# rc2014_6809.net
KiCad netlist of a schematic drawn in EAGLE
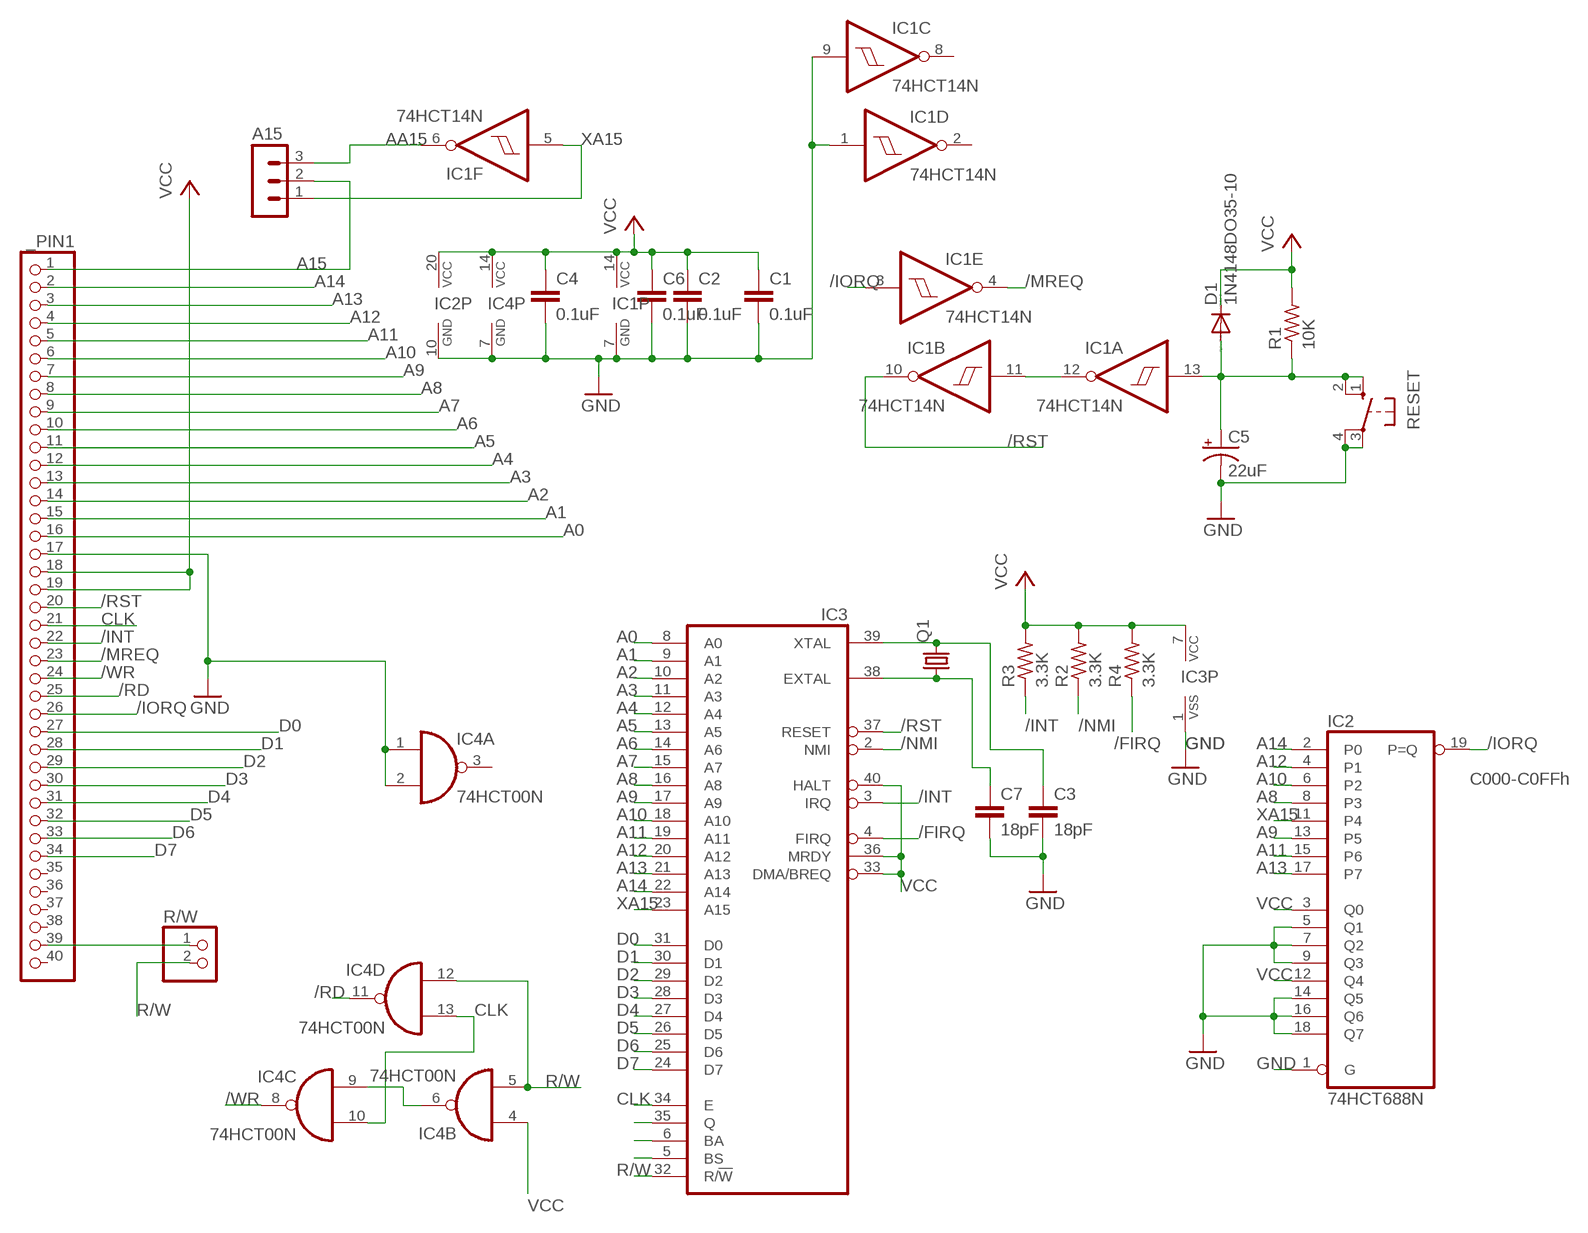
[diagram p0: schematic, sheet 1]

(export (version "E")
  (design (tool "Eeschema 10.0.6"))
  (components
    (comp (ref "A15")
      (value "MA03-1")
      (footprint "eagle-import:MA03-1")
      (libsource (lib "eagle-import") (part "MA03-1"))
    )
    (comp (ref "C1")
      (value "0.1uF")
      (footprint "eagle-import:C050-024X044")
      (libsource (lib "eagle-import") (part "C-EU050-024X044"))
    )
    (comp (ref "C2")
      (value "0.1uF")
      (footprint "eagle-import:C050-024X044")
      (libsource (lib "eagle-import") (part "C-EU050-024X044"))
    )
    (comp (ref "C3")
      (value "18pF")
      (footprint "eagle-import:C050-024X044")
      (libsource (lib "eagle-import") (part "C-EU050-024X044"))
    )
    (comp (ref "C4")
      (value "0.1uF")
      (footprint "eagle-import:C050-024X044")
      (libsource (lib "eagle-import") (part "C-EU050-024X044"))
    )
    (comp (ref "C5")
      (value "22uF")
      (footprint "eagle-import:TAP5-80")
      (libsource (lib "eagle-import") (part "CPOL-USTAP5-80"))
    )
    (comp (ref "C6")
      (value "0.1uF")
      (footprint "eagle-import:C050-024X044")
      (libsource (lib "eagle-import") (part "C-EU050-024X044"))
    )
    (comp (ref "C7")
      (value "18pF")
      (footprint "eagle-import:C050-024X044")
      (libsource (lib "eagle-import") (part "C-EU050-024X044"))
    )
    (comp (ref "D1")
      (value "1N4148DO35-10")
      (footprint "eagle-import:DO35-10")
      (libsource (lib "eagle-import") (part "1N4148DO35-10"))
    )
    (comp (ref "IC1")
      (value "74HCT14N")
      (footprint "eagle-import:DIL14")
      (libsource (lib "eagle-import") (part "7414NHCT"))
    )
    (comp (ref "IC2")
      (value "74HCT688N")
      (footprint "eagle-import:DIL20")
      (libsource (lib "eagle-import") (part "74688NHCT"))
    )
    (comp (ref "IC3")
      (value "6809")
      (footprint "eagle-import:DIL40")
      (fields (field (name "MF") "NTE ELECTRONICS") (field (name "MPN") "NTE6809"))
      (libsource (lib "eagle-import") (part "6809"))
    )
    (comp (ref "IC4")
      (value "74HCT00N")
      (footprint "eagle-import:DIL14")
      (libsource (lib "eagle-import") (part "7400NHCT"))
    )
    (comp (ref "Q1")
      (value "CRYSTALHC49S")
      (footprint "eagle-import:HC49_S")
      (libsource (lib "eagle-import") (part "CRYSTALHC49S"))
    )
    (comp (ref "R/W")
      (value "PINHD-1X2")
      (footprint "eagle-import:1X02")
      (libsource (lib "eagle-import") (part "PINHD-1X2"))
    )
    (comp (ref "R1")
      (value "10K")
      (footprint "eagle-import:0207_10")
      (libsource (lib "eagle-import") (part "R-US_0207/10"))
    )
    (comp (ref "R2")
      (value "3.3K")
      (footprint "eagle-import:0207_10")
      (libsource (lib "eagle-import") (part "R-US_0207/10"))
    )
    (comp (ref "R3")
      (value "3.3K")
      (footprint "eagle-import:0207_10")
      (libsource (lib "eagle-import") (part "R-US_0207/10"))
    )
    (comp (ref "R4")
      (value "3.3K")
      (footprint "eagle-import:0207_10")
      (libsource (lib "eagle-import") (part "R-US_0207/10"))
    )
    (comp (ref "RESET")
      (value "10-XX")
      (footprint "eagle-import:B3F-10XX")
      (fields (field (name "MPN") "B3F-1000"))
      (libsource (lib "eagle-import") (part "10-XX"))
    )
    (comp (ref "_PIN1")
      (value "PINHD-1X40")
      (footprint "eagle-import:1X40")
      (libsource (lib "eagle-import") (part "PINHD-1X40"))
    )
  )
  (nets
    (net (code "1") (name "/A0") (class "Default")
      (node (ref "IC3") (pin "8") (pinfunction "A0_8") (pintype "tri_state"))
      (node (ref "_PIN1") (pin "16") (pinfunction "16_16") (pintype "passive"))
    )
    (net (code "2") (name "/A1") (class "Default")
      (node (ref "IC3") (pin "9") (pinfunction "A1_9") (pintype "tri_state"))
      (node (ref "_PIN1") (pin "15") (pinfunction "15_15") (pintype "passive"))
    )
    (net (code "3") (name "/A2") (class "Default")
      (node (ref "IC3") (pin "10") (pinfunction "A2_10") (pintype "tri_state"))
      (node (ref "_PIN1") (pin "14") (pinfunction "14_14") (pintype "passive"))
    )
    (net (code "4") (name "/A3") (class "Default")
      (node (ref "IC3") (pin "11") (pinfunction "A3_11") (pintype "tri_state"))
      (node (ref "_PIN1") (pin "13") (pinfunction "13_13") (pintype "passive"))
    )
    (net (code "5") (name "/A4") (class "Default")
      (node (ref "IC3") (pin "12") (pinfunction "A4_12") (pintype "tri_state"))
      (node (ref "_PIN1") (pin "12") (pinfunction "12_12") (pintype "passive"))
    )
    (net (code "6") (name "/A5") (class "Default")
      (node (ref "IC3") (pin "13") (pinfunction "A5_13") (pintype "tri_state"))
      (node (ref "_PIN1") (pin "11") (pinfunction "11_11") (pintype "passive"))
    )
    (net (code "7") (name "/A6") (class "Default")
      (node (ref "IC3") (pin "14") (pinfunction "A6_14") (pintype "tri_state"))
      (node (ref "_PIN1") (pin "10") (pinfunction "10_10") (pintype "passive"))
    )
    (net (code "8") (name "/A7") (class "Default")
      (node (ref "IC3") (pin "15") (pinfunction "A7_15") (pintype "tri_state"))
      (node (ref "_PIN1") (pin "9") (pinfunction "9_9") (pintype "passive"))
    )
    (net (code "9") (name "/A8") (class "Default")
      (node (ref "IC2") (pin "8") (pinfunction "P3_8") (pintype "input"))
      (node (ref "IC3") (pin "16") (pinfunction "A8_16") (pintype "tri_state"))
      (node (ref "_PIN1") (pin "8") (pinfunction "8_8") (pintype "passive"))
    )
    (net (code "10") (name "/A9") (class "Default")
      (node (ref "IC2") (pin "13") (pinfunction "P5_13") (pintype "input"))
      (node (ref "IC3") (pin "17") (pinfunction "A9_17") (pintype "tri_state"))
      (node (ref "_PIN1") (pin "7") (pinfunction "7_7") (pintype "passive"))
    )
    (net (code "11") (name "/A10") (class "Default")
      (node (ref "IC2") (pin "6") (pinfunction "P2_6") (pintype "input"))
      (node (ref "IC3") (pin "18") (pinfunction "A10_18") (pintype "tri_state"))
      (node (ref "_PIN1") (pin "6") (pinfunction "6_6") (pintype "passive"))
    )
    (net (code "12") (name "/A11") (class "Default")
      (node (ref "IC2") (pin "15") (pinfunction "P6_15") (pintype "input"))
      (node (ref "IC3") (pin "19") (pinfunction "A11_19") (pintype "tri_state"))
      (node (ref "_PIN1") (pin "5") (pinfunction "5_5") (pintype "passive"))
    )
    (net (code "13") (name "/A12") (class "Default")
      (node (ref "IC2") (pin "4") (pinfunction "P1_4") (pintype "input"))
      (node (ref "IC3") (pin "20") (pinfunction "A12_20") (pintype "tri_state"))
      (node (ref "_PIN1") (pin "4") (pinfunction "4_4") (pintype "passive"))
    )
    (net (code "14") (name "/A13") (class "Default")
      (node (ref "IC2") (pin "17") (pinfunction "P7_17") (pintype "input"))
      (node (ref "IC3") (pin "21") (pinfunction "A13_21") (pintype "tri_state"))
      (node (ref "_PIN1") (pin "3") (pinfunction "3_3") (pintype "passive"))
    )
    (net (code "15") (name "/A14") (class "Default")
      (node (ref "IC2") (pin "2") (pinfunction "P0_2") (pintype "input"))
      (node (ref "IC3") (pin "22") (pinfunction "A14_22") (pintype "tri_state"))
      (node (ref "_PIN1") (pin "2") (pinfunction "2_2") (pintype "passive"))
    )
    (net (code "16") (name "/A15") (class "Default")
      (node (ref "A15") (pin "2") (pinfunction "2_2") (pintype "passive"))
      (node (ref "_PIN1") (pin "1") (pinfunction "1_1") (pintype "passive"))
    )
    (net (code "17") (name "/AA15") (class "Default")
      (node (ref "A15") (pin "3") (pinfunction "3_3") (pintype "passive"))
      (node (ref "IC1") (pin "6") (pinfunction "O_6") (pintype "output"))
    )
    (net (code "18") (name "/CLK") (class "Default")
      (node (ref "IC3") (pin "34") (pinfunction "E_34") (pintype "output"))
      (node (ref "IC4") (pin "10") (pinfunction "I1_10") (pintype "input"))
      (node (ref "IC4") (pin "13") (pinfunction "I1_13") (pintype "input"))
      (node (ref "_PIN1") (pin "21") (pinfunction "21_21") (pintype "passive"))
    )
    (net (code "19") (name "/D0") (class "Default")
      (node (ref "IC3") (pin "31") (pinfunction "D0_31") (pintype "bidirectional"))
      (node (ref "_PIN1") (pin "27") (pinfunction "27_27") (pintype "passive"))
    )
    (net (code "20") (name "/D1") (class "Default")
      (node (ref "IC3") (pin "30") (pinfunction "D1_30") (pintype "bidirectional"))
      (node (ref "_PIN1") (pin "28") (pinfunction "28_28") (pintype "passive"))
    )
    (net (code "21") (name "/D2") (class "Default")
      (node (ref "IC3") (pin "29") (pinfunction "D2_29") (pintype "bidirectional"))
      (node (ref "_PIN1") (pin "29") (pinfunction "29_29") (pintype "passive"))
    )
    (net (code "22") (name "/D3") (class "Default")
      (node (ref "IC3") (pin "28") (pinfunction "D3_28") (pintype "bidirectional"))
      (node (ref "_PIN1") (pin "30") (pinfunction "30_30") (pintype "passive"))
    )
    (net (code "23") (name "/D4") (class "Default")
      (node (ref "IC3") (pin "27") (pinfunction "D4_27") (pintype "bidirectional"))
      (node (ref "_PIN1") (pin "31") (pinfunction "31_31") (pintype "passive"))
    )
    (net (code "24") (name "/D5") (class "Default")
      (node (ref "IC3") (pin "26") (pinfunction "D5_26") (pintype "bidirectional"))
      (node (ref "_PIN1") (pin "32") (pinfunction "32_32") (pintype "passive"))
    )
    (net (code "25") (name "/D6") (class "Default")
      (node (ref "IC3") (pin "25") (pinfunction "D6_25") (pintype "bidirectional"))
      (node (ref "_PIN1") (pin "33") (pinfunction "33_33") (pintype "passive"))
    )
    (net (code "26") (name "/D7") (class "Default")
      (node (ref "IC3") (pin "24") (pinfunction "D7_24") (pintype "bidirectional"))
      (node (ref "_PIN1") (pin "34") (pinfunction "34_34") (pintype "passive"))
    )
    (net (code "27") (name "/R{slash}W") (class "Default")
      (node (ref "IC3") (pin "32") (pinfunction "R/~{W}_32") (pintype "output"))
      (node (ref "IC4") (pin "12") (pinfunction "I0_12") (pintype "input"))
      (node (ref "IC4") (pin "5") (pinfunction "I1_5") (pintype "input"))
      (node (ref "R/W") (pin "2") (pinfunction "2_2") (pintype "passive"))
    )
    (net (code "28") (name "/XA15") (class "Default")
      (node (ref "A15") (pin "1") (pinfunction "1_1") (pintype "passive"))
      (node (ref "IC1") (pin "5") (pinfunction "I_5") (pintype "input"))
      (node (ref "IC2") (pin "11") (pinfunction "P4_11") (pintype "input"))
      (node (ref "IC3") (pin "23") (pinfunction "A15_23") (pintype "tri_state"))
    )
    (net (code "29") (name "/{slash}FIRQ") (class "Default")
      (node (ref "IC3") (pin "4") (pinfunction "FIRQ_4") (pintype "input"))
      (node (ref "R4") (pin "1") (pinfunction "1_1") (pintype "passive"))
    )
    (net (code "30") (name "/{slash}INT") (class "Default")
      (node (ref "IC3") (pin "3") (pinfunction "IRQ_3") (pintype "input"))
      (node (ref "R3") (pin "1") (pinfunction "1_1") (pintype "passive"))
      (node (ref "_PIN1") (pin "22") (pinfunction "22_22") (pintype "passive"))
    )
    (net (code "31") (name "/{slash}IORQ") (class "Default")
      (node (ref "IC1") (pin "3") (pinfunction "I_3") (pintype "input"))
      (node (ref "IC2") (pin "19") (pinfunction "P=Q_19") (pintype "output"))
      (node (ref "_PIN1") (pin "26") (pinfunction "26_26") (pintype "passive"))
    )
    (net (code "32") (name "/{slash}MREQ") (class "Default")
      (node (ref "IC1") (pin "4") (pinfunction "O_4") (pintype "output"))
      (node (ref "_PIN1") (pin "23") (pinfunction "23_23") (pintype "passive"))
    )
    (net (code "33") (name "/{slash}NMI") (class "Default")
      (node (ref "IC3") (pin "2") (pinfunction "NMI_2") (pintype "input"))
      (node (ref "R2") (pin "1") (pinfunction "1_1") (pintype "passive"))
    )
    (net (code "34") (name "/{slash}RD") (class "Default")
      (node (ref "IC4") (pin "11") (pinfunction "O_11") (pintype "output"))
      (node (ref "_PIN1") (pin "25") (pinfunction "25_25") (pintype "passive"))
    )
    (net (code "35") (name "/{slash}RST") (class "Default")
      (node (ref "IC1") (pin "10") (pinfunction "O_10") (pintype "output"))
      (node (ref "IC3") (pin "37") (pinfunction "RESET_37") (pintype "input"))
      (node (ref "_PIN1") (pin "20") (pinfunction "20_20") (pintype "passive"))
    )
    (net (code "36") (name "/{slash}WR") (class "Default")
      (node (ref "IC4") (pin "8") (pinfunction "O_8") (pintype "output"))
      (node (ref "_PIN1") (pin "24") (pinfunction "24_24") (pintype "passive"))
    )
    (net (code "37") (name "GND") (class "Default")
      (node (ref "C1") (pin "2") (pinfunction "2_2") (pintype "passive"))
      (node (ref "C2") (pin "2") (pinfunction "2_2") (pintype "passive"))
      (node (ref "C3") (pin "2") (pinfunction "2_2") (pintype "passive"))
      (node (ref "C4") (pin "2") (pinfunction "2_2") (pintype "passive"))
      (node (ref "C5") (pin "-") (pinfunction "-_-") (pintype "passive"))
      (node (ref "C6") (pin "2") (pinfunction "2_2") (pintype "passive"))
      (node (ref "C7") (pin "2") (pinfunction "2_2") (pintype "passive"))
      (node (ref "IC1") (pin "1") (pinfunction "I_1") (pintype "input"))
      (node (ref "IC1") (pin "7") (pinfunction "GND_7") (pintype "power_in"))
      (node (ref "IC1") (pin "9") (pinfunction "I_9") (pintype "input"))
      (node (ref "IC2") (pin "1") (pinfunction "G_1") (pintype "input"))
      (node (ref "IC2") (pin "10") (pinfunction "GND_10") (pintype "power_in"))
      (node (ref "IC2") (pin "14") (pinfunction "Q5_14") (pintype "input"))
      (node (ref "IC2") (pin "16") (pinfunction "Q6_16") (pintype "input"))
      (node (ref "IC2") (pin "18") (pinfunction "Q7_18") (pintype "input"))
      (node (ref "IC2") (pin "5") (pinfunction "Q1_5") (pintype "input"))
      (node (ref "IC2") (pin "7") (pinfunction "Q2_7") (pintype "input"))
      (node (ref "IC2") (pin "9") (pinfunction "Q3_9") (pintype "input"))
      (node (ref "IC3") (pin "1") (pinfunction "VSS_1") (pintype "power_in"))
      (node (ref "IC4") (pin "1") (pinfunction "I0_1") (pintype "input"))
      (node (ref "IC4") (pin "2") (pinfunction "I1_2") (pintype "input"))
      (node (ref "IC4") (pin "7") (pinfunction "GND_7") (pintype "power_in"))
      (node (ref "RESET") (pin "3") (pinfunction "P_3") (pintype "passive"))
      (node (ref "RESET") (pin "4") (pinfunction "P1_4") (pintype "passive"))
      (node (ref "_PIN1") (pin "17") (pinfunction "17_17") (pintype "passive"))
    )
    (net (code "38") (name "Net-(IC1A-I)") (class "Default")
      (node (ref "C5") (pin "+") (pinfunction "+_+") (pintype "passive"))
      (node (ref "D1") (pin "A") (pinfunction "A_A") (pintype "passive"))
      (node (ref "IC1") (pin "13") (pinfunction "I_13") (pintype "input"))
      (node (ref "R1") (pin "1") (pinfunction "1_1") (pintype "passive"))
      (node (ref "RESET") (pin "1") (pinfunction "S_1") (pintype "passive"))
      (node (ref "RESET") (pin "2") (pinfunction "S1_2") (pintype "passive"))
    )
    (net (code "39") (name "Net-(IC1A-O)") (class "Default")
      (node (ref "IC1") (pin "11") (pinfunction "I_11") (pintype "input"))
      (node (ref "IC1") (pin "12") (pinfunction "O_12") (pintype "output"))
    )
    (net (code "40") (name "Net-(IC3A-EXTAL)") (class "Default")
      (node (ref "C7") (pin "1") (pinfunction "1_1") (pintype "passive"))
      (node (ref "IC3") (pin "38") (pinfunction "EXTAL_38") (pintype "input"))
      (node (ref "Q1") (pin "1") (pinfunction "1_1") (pintype "passive"))
    )
    (net (code "41") (name "Net-(IC3A-XTAL)") (class "Default")
      (node (ref "C3") (pin "1") (pinfunction "1_1") (pintype "passive"))
      (node (ref "IC3") (pin "39") (pinfunction "XTAL_39") (pintype "input"))
      (node (ref "Q1") (pin "2") (pinfunction "2_2") (pintype "passive"))
    )
    (net (code "42") (name "Net-(IC4B-O)") (class "Default")
      (node (ref "IC4") (pin "6") (pinfunction "O_6") (pintype "output"))
      (node (ref "IC4") (pin "9") (pinfunction "I0_9") (pintype "input"))
    )
    (net (code "43") (name "Net-(R/W-Pad1)") (class "Default")
      (node (ref "R/W") (pin "1") (pinfunction "1_1") (pintype "passive"))
      (node (ref "_PIN1") (pin "39") (pinfunction "39_39") (pintype "passive"))
    )
    (net (code "44") (name "VCC") (class "Default")
      (node (ref "C1") (pin "1") (pinfunction "1_1") (pintype "passive"))
      (node (ref "C2") (pin "1") (pinfunction "1_1") (pintype "passive"))
      (node (ref "C4") (pin "1") (pinfunction "1_1") (pintype "passive"))
      (node (ref "C6") (pin "1") (pinfunction "1_1") (pintype "passive"))
      (node (ref "D1") (pin "C") (pinfunction "C_C") (pintype "passive"))
      (node (ref "IC1") (pin "14") (pinfunction "VCC_14") (pintype "power_in"))
      (node (ref "IC2") (pin "12") (pinfunction "Q4_12") (pintype "input"))
      (node (ref "IC2") (pin "20") (pinfunction "VCC_20") (pintype "power_in"))
      (node (ref "IC2") (pin "3") (pinfunction "Q0_3") (pintype "input"))
      (node (ref "IC3") (pin "33") (pinfunction "DMA/BREQ_33") (pintype "input"))
      (node (ref "IC3") (pin "36") (pinfunction "MRDY_36") (pintype "input"))
      (node (ref "IC3") (pin "40") (pinfunction "HALT_40") (pintype "input"))
      (node (ref "IC3") (pin "7") (pinfunction "VCC_7") (pintype "power_in"))
      (node (ref "IC4") (pin "14") (pinfunction "VCC_14") (pintype "power_in"))
      (node (ref "IC4") (pin "4") (pinfunction "I0_4") (pintype "input"))
      (node (ref "R1") (pin "2") (pinfunction "2_2") (pintype "passive"))
      (node (ref "R2") (pin "2") (pinfunction "2_2") (pintype "passive"))
      (node (ref "R3") (pin "2") (pinfunction "2_2") (pintype "passive"))
      (node (ref "R4") (pin "2") (pinfunction "2_2") (pintype "passive"))
      (node (ref "_PIN1") (pin "18") (pinfunction "18_18") (pintype "passive"))
      (node (ref "_PIN1") (pin "19") (pinfunction "19_19") (pintype "passive"))
    )
    (net (code "45") (name "unconnected-(IC1C-O-Pad8)") (class "Default")
      (node (ref "IC1") (pin "8") (pinfunction "O_8") (pintype "output"))
    )
    (net (code "46") (name "unconnected-(IC1D-O-Pad2)") (class "Default")
      (node (ref "IC1") (pin "2") (pinfunction "O_2") (pintype "output"))
    )
    (net (code "47") (name "unconnected-(IC3A-BA-Pad6)") (class "Default")
      (node (ref "IC3") (pin "6") (pinfunction "BA_6") (pintype "output"))
    )
    (net (code "48") (name "unconnected-(IC3A-BS-Pad5)") (class "Default")
      (node (ref "IC3") (pin "5") (pinfunction "BS_5") (pintype "output"))
    )
    (net (code "49") (name "unconnected-(IC3A-Q-Pad35)") (class "Default")
      (node (ref "IC3") (pin "35") (pinfunction "Q_35") (pintype "output"))
    )
    (net (code "50") (name "unconnected-(IC4A-O-Pad3)") (class "Default")
      (node (ref "IC4") (pin "3") (pinfunction "O_3") (pintype "output"))
    )
    (net (code "51") (name "unconnected-(_PIN1-Pad35)") (class "Default")
      (node (ref "_PIN1") (pin "35") (pinfunction "35_35") (pintype "passive"))
    )
    (net (code "52") (name "unconnected-(_PIN1-Pad36)") (class "Default")
      (node (ref "_PIN1") (pin "36") (pinfunction "36_36") (pintype "passive"))
    )
    (net (code "53") (name "unconnected-(_PIN1-Pad37)") (class "Default")
      (node (ref "_PIN1") (pin "37") (pinfunction "37_37") (pintype "passive"))
    )
    (net (code "54") (name "unconnected-(_PIN1-Pad38)") (class "Default")
      (node (ref "_PIN1") (pin "38") (pinfunction "38_38") (pintype "passive"))
    )
    (net (code "55") (name "unconnected-(_PIN1-Pad40)") (class "Default")
      (node (ref "_PIN1") (pin "40") (pinfunction "40_40") (pintype "passive"))
    )
  )
)
